# CAN-D_Helper_Rev1.net
KiCad netlist of a schematic drawn in EAGLE
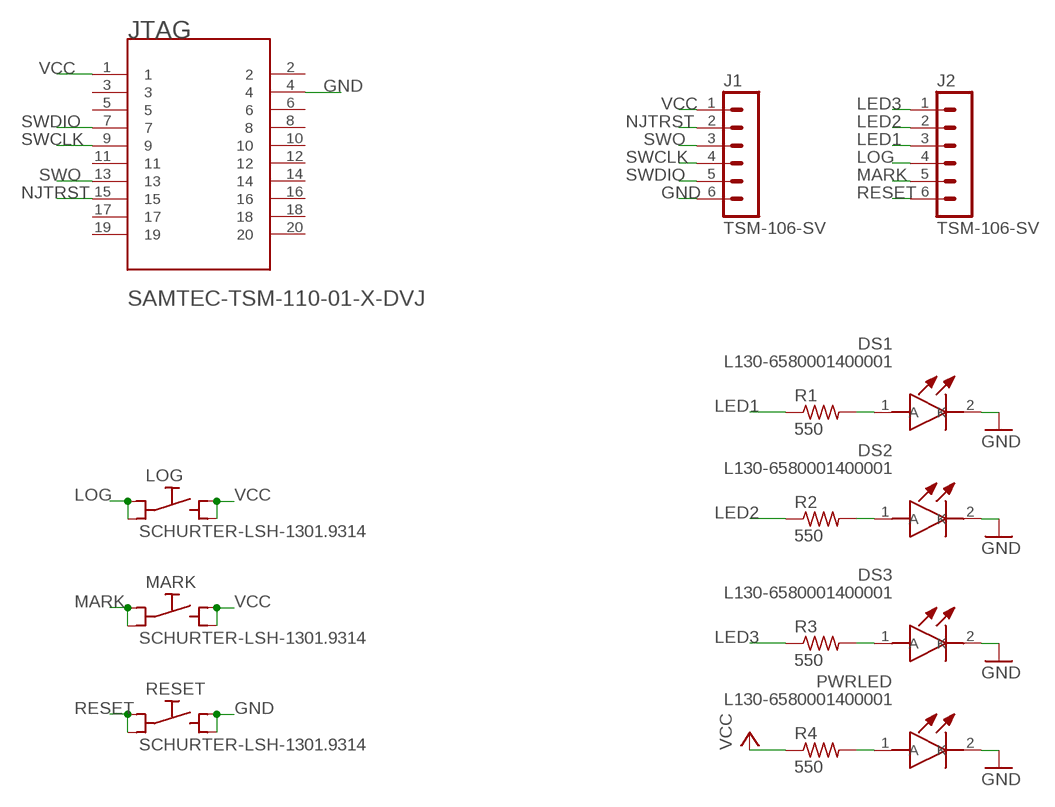
[diagram p0: schematic, sheet 1]

(export (version "E")
  (design (tool "Eeschema 10.0.6"))
  (components
    (comp (ref "DS1")
      (value "L130-6580001400001")
      (footprint "eagle-import:L130-6580001400001")
      (fields
        (field (name "MOUSER_PART_NUMBER") "997-L130-65800014001")
        (field (name "RS_PART_NUMBER") "1709867")
      )
      (libsource (lib "eagle-import") (part "L130-6580001400001"))
    )
    (comp (ref "DS2")
      (value "L130-6580001400001")
      (footprint "eagle-import:L130-6580001400001")
      (fields
        (field (name "MOUSER_PART_NUMBER") "997-L130-65800014001")
        (field (name "RS_PART_NUMBER") "1709867")
      )
      (libsource (lib "eagle-import") (part "L130-6580001400001"))
    )
    (comp (ref "DS3")
      (value "L130-6580001400001")
      (footprint "eagle-import:L130-6580001400001")
      (fields
        (field (name "MOUSER_PART_NUMBER") "997-L130-65800014001")
        (field (name "RS_PART_NUMBER") "1709867")
      )
      (libsource (lib "eagle-import") (part "L130-6580001400001"))
    )
    (comp (ref "J1")
      (value "TSM-106-SV")
      (footprint "eagle-import:TSM-106-SV")
      (libsource (lib "eagle-import") (part "TSM-106-SV"))
    )
    (comp (ref "J2")
      (value "TSM-106-SV")
      (footprint "eagle-import:TSM-106-SV")
      (libsource (lib "eagle-import") (part "TSM-106-SV"))
    )
    (comp (ref "JTAG")
      (value "SAMTEC-TSM-110-01-X-DVJ")
      (footprint "eagle-import:SAMTEC-TSM-110-01-X-DV")
      (fields
        (field (name "DIGI-KEY_PART_NUMBER") "SAM14887CT-ND")
        (field (name "MF") "Samtec Inc.")
        (field (name "MP") "TSM-110-01-T-DV-TR")
      )
      (libsource (lib "eagle-import") (part "SAMTEC-TSM-110-01-X-DVJ"))
    )
    (comp (ref "LOG")
      (value "SCHURTER-LSH-1301.9314")
      (footprint "eagle-import:LSH")
      (libsource (lib "eagle-import") (part "SCHURTER-LSH-1301.9314"))
    )
    (comp (ref "MARK")
      (value "SCHURTER-LSH-1301.9314")
      (footprint "eagle-import:LSH")
      (libsource (lib "eagle-import") (part "SCHURTER-LSH-1301.9314"))
    )
    (comp (ref "PWRLED")
      (value "L130-6580001400001")
      (footprint "eagle-import:L130-6580001400001")
      (fields
        (field (name "MOUSER_PART_NUMBER") "997-L130-65800014001")
        (field (name "RS_PART_NUMBER") "1709867")
      )
      (libsource (lib "eagle-import") (part "L130-6580001400001"))
    )
    (comp (ref "R1")
      (value "550")
      (footprint "eagle-import:R0603")
      (libsource (lib "eagle-import") (part "R-US_R0603"))
    )
    (comp (ref "R2")
      (value "550")
      (footprint "eagle-import:R0603")
      (libsource (lib "eagle-import") (part "R-US_R0603"))
    )
    (comp (ref "R3")
      (value "550")
      (footprint "eagle-import:R0603")
      (libsource (lib "eagle-import") (part "R-US_R0603"))
    )
    (comp (ref "R4")
      (value "550")
      (footprint "eagle-import:R0603")
      (libsource (lib "eagle-import") (part "R-US_R0603"))
    )
    (comp (ref "RESET")
      (value "SCHURTER-LSH-1301.9314")
      (footprint "eagle-import:LSH")
      (libsource (lib "eagle-import") (part "SCHURTER-LSH-1301.9314"))
    )
  )
  (nets
    (net (code "1") (name "/LED1") (class "Default")
      (node (ref "J2") (pin "3") (pinfunction "3_3") (pintype "passive"))
      (node (ref "R1") (pin "1") (pinfunction "1_1") (pintype "passive"))
    )
    (net (code "2") (name "/LED2") (class "Default")
      (node (ref "J2") (pin "2") (pinfunction "2_2") (pintype "passive"))
      (node (ref "R2") (pin "1") (pinfunction "1_1") (pintype "passive"))
    )
    (net (code "3") (name "/LED3") (class "Default")
      (node (ref "J2") (pin "1") (pinfunction "1_1") (pintype "passive"))
      (node (ref "R3") (pin "1") (pinfunction "1_1") (pintype "passive"))
    )
    (net (code "4") (name "/LOG") (class "Default")
      (node (ref "J2") (pin "4") (pinfunction "4_4") (pintype "passive"))
      (node (ref "LOG") (pin "C1") (pinfunction "C_C1") (pintype "passive"))
      (node (ref "LOG") (pin "C2") (pinfunction "C_C2") (pintype "passive"))
    )
    (net (code "5") (name "/MARK") (class "Default")
      (node (ref "J2") (pin "5") (pinfunction "5_5") (pintype "passive"))
      (node (ref "MARK") (pin "C1") (pinfunction "C_C1") (pintype "passive"))
      (node (ref "MARK") (pin "C2") (pinfunction "C_C2") (pintype "passive"))
    )
    (net (code "6") (name "/NJTRST") (class "Default")
      (node (ref "J1") (pin "2") (pinfunction "2_2") (pintype "passive"))
      (node (ref "JTAG") (pin "15") (pinfunction "15_15") (pintype "passive"))
    )
    (net (code "7") (name "/RESET") (class "Default")
      (node (ref "J2") (pin "6") (pinfunction "6_6") (pintype "passive"))
      (node (ref "RESET") (pin "C1") (pinfunction "C_C1") (pintype "passive"))
      (node (ref "RESET") (pin "C2") (pinfunction "C_C2") (pintype "passive"))
    )
    (net (code "8") (name "/SWCLK") (class "Default")
      (node (ref "J1") (pin "4") (pinfunction "4_4") (pintype "passive"))
      (node (ref "JTAG") (pin "9") (pinfunction "9_9") (pintype "passive"))
    )
    (net (code "9") (name "/SWDIO") (class "Default")
      (node (ref "J1") (pin "5") (pinfunction "5_5") (pintype "passive"))
      (node (ref "JTAG") (pin "7") (pinfunction "7_7") (pintype "passive"))
    )
    (net (code "10") (name "/SWO") (class "Default")
      (node (ref "J1") (pin "3") (pinfunction "3_3") (pintype "passive"))
      (node (ref "JTAG") (pin "13") (pinfunction "13_13") (pintype "passive"))
    )
    (net (code "11") (name "GND") (class "Default")
      (node (ref "DS1") (pin "2") (pinfunction "K_2") (pintype "bidirectional"))
      (node (ref "DS2") (pin "2") (pinfunction "K_2") (pintype "bidirectional"))
      (node (ref "DS3") (pin "2") (pinfunction "K_2") (pintype "bidirectional"))
      (node (ref "J1") (pin "6") (pinfunction "6_6") (pintype "passive"))
      (node (ref "JTAG") (pin "4") (pinfunction "4_4") (pintype "passive"))
      (node (ref "PWRLED") (pin "2") (pinfunction "K_2") (pintype "bidirectional"))
      (node (ref "RESET") (pin "NO1") (pinfunction "NO_NO1") (pintype "passive"))
      (node (ref "RESET") (pin "NO2") (pinfunction "NO_NO2") (pintype "passive"))
    )
    (net (code "12") (name "Net-(DS1-A)") (class "Default")
      (node (ref "DS1") (pin "1") (pinfunction "A_1") (pintype "bidirectional"))
      (node (ref "R1") (pin "2") (pinfunction "2_2") (pintype "passive"))
    )
    (net (code "13") (name "Net-(DS2-A)") (class "Default")
      (node (ref "DS2") (pin "1") (pinfunction "A_1") (pintype "bidirectional"))
      (node (ref "R2") (pin "2") (pinfunction "2_2") (pintype "passive"))
    )
    (net (code "14") (name "Net-(DS3-A)") (class "Default")
      (node (ref "DS3") (pin "1") (pinfunction "A_1") (pintype "bidirectional"))
      (node (ref "R3") (pin "2") (pinfunction "2_2") (pintype "passive"))
    )
    (net (code "15") (name "Net-(PWRLED-A)") (class "Default")
      (node (ref "PWRLED") (pin "1") (pinfunction "A_1") (pintype "bidirectional"))
      (node (ref "R4") (pin "2") (pinfunction "2_2") (pintype "passive"))
    )
    (net (code "16") (name "VCC") (class "Default")
      (node (ref "J1") (pin "1") (pinfunction "1_1") (pintype "passive"))
      (node (ref "JTAG") (pin "1") (pinfunction "1_1") (pintype "passive"))
      (node (ref "LOG") (pin "NO1") (pinfunction "NO_NO1") (pintype "passive"))
      (node (ref "LOG") (pin "NO2") (pinfunction "NO_NO2") (pintype "passive"))
      (node (ref "MARK") (pin "NO1") (pinfunction "NO_NO1") (pintype "passive"))
      (node (ref "MARK") (pin "NO2") (pinfunction "NO_NO2") (pintype "passive"))
      (node (ref "R4") (pin "1") (pinfunction "1_1") (pintype "passive"))
    )
    (net (code "17") (name "unconnected-(JTAG-Pad2)") (class "Default")
      (node (ref "JTAG") (pin "2") (pinfunction "2_2") (pintype "passive"))
    )
    (net (code "18") (name "unconnected-(JTAG-Pad3)") (class "Default")
      (node (ref "JTAG") (pin "3") (pinfunction "3_3") (pintype "passive"))
    )
    (net (code "19") (name "unconnected-(JTAG-Pad5)") (class "Default")
      (node (ref "JTAG") (pin "5") (pinfunction "5_5") (pintype "passive"))
    )
    (net (code "20") (name "unconnected-(JTAG-Pad6)") (class "Default")
      (node (ref "JTAG") (pin "6") (pinfunction "6_6") (pintype "passive"))
    )
    (net (code "21") (name "unconnected-(JTAG-Pad8)") (class "Default")
      (node (ref "JTAG") (pin "8") (pinfunction "8_8") (pintype "passive"))
    )
    (net (code "22") (name "unconnected-(JTAG-Pad10)") (class "Default")
      (node (ref "JTAG") (pin "10") (pinfunction "10_10") (pintype "passive"))
    )
    (net (code "23") (name "unconnected-(JTAG-Pad11)") (class "Default")
      (node (ref "JTAG") (pin "11") (pinfunction "11_11") (pintype "passive"))
    )
    (net (code "24") (name "unconnected-(JTAG-Pad12)") (class "Default")
      (node (ref "JTAG") (pin "12") (pinfunction "12_12") (pintype "passive"))
    )
    (net (code "25") (name "unconnected-(JTAG-Pad14)") (class "Default")
      (node (ref "JTAG") (pin "14") (pinfunction "14_14") (pintype "passive"))
    )
    (net (code "26") (name "unconnected-(JTAG-Pad16)") (class "Default")
      (node (ref "JTAG") (pin "16") (pinfunction "16_16") (pintype "passive"))
    )
    (net (code "27") (name "unconnected-(JTAG-Pad17)") (class "Default")
      (node (ref "JTAG") (pin "17") (pinfunction "17_17") (pintype "passive"))
    )
    (net (code "28") (name "unconnected-(JTAG-Pad18)") (class "Default")
      (node (ref "JTAG") (pin "18") (pinfunction "18_18") (pintype "passive"))
    )
    (net (code "29") (name "unconnected-(JTAG-Pad19)") (class "Default")
      (node (ref "JTAG") (pin "19") (pinfunction "19_19") (pintype "passive"))
    )
    (net (code "30") (name "unconnected-(JTAG-Pad20)") (class "Default")
      (node (ref "JTAG") (pin "20") (pinfunction "20_20") (pintype "passive"))
    )
  )
)
